# ADC.net
KiCad netlist of a schematic drawn in Altium Designer
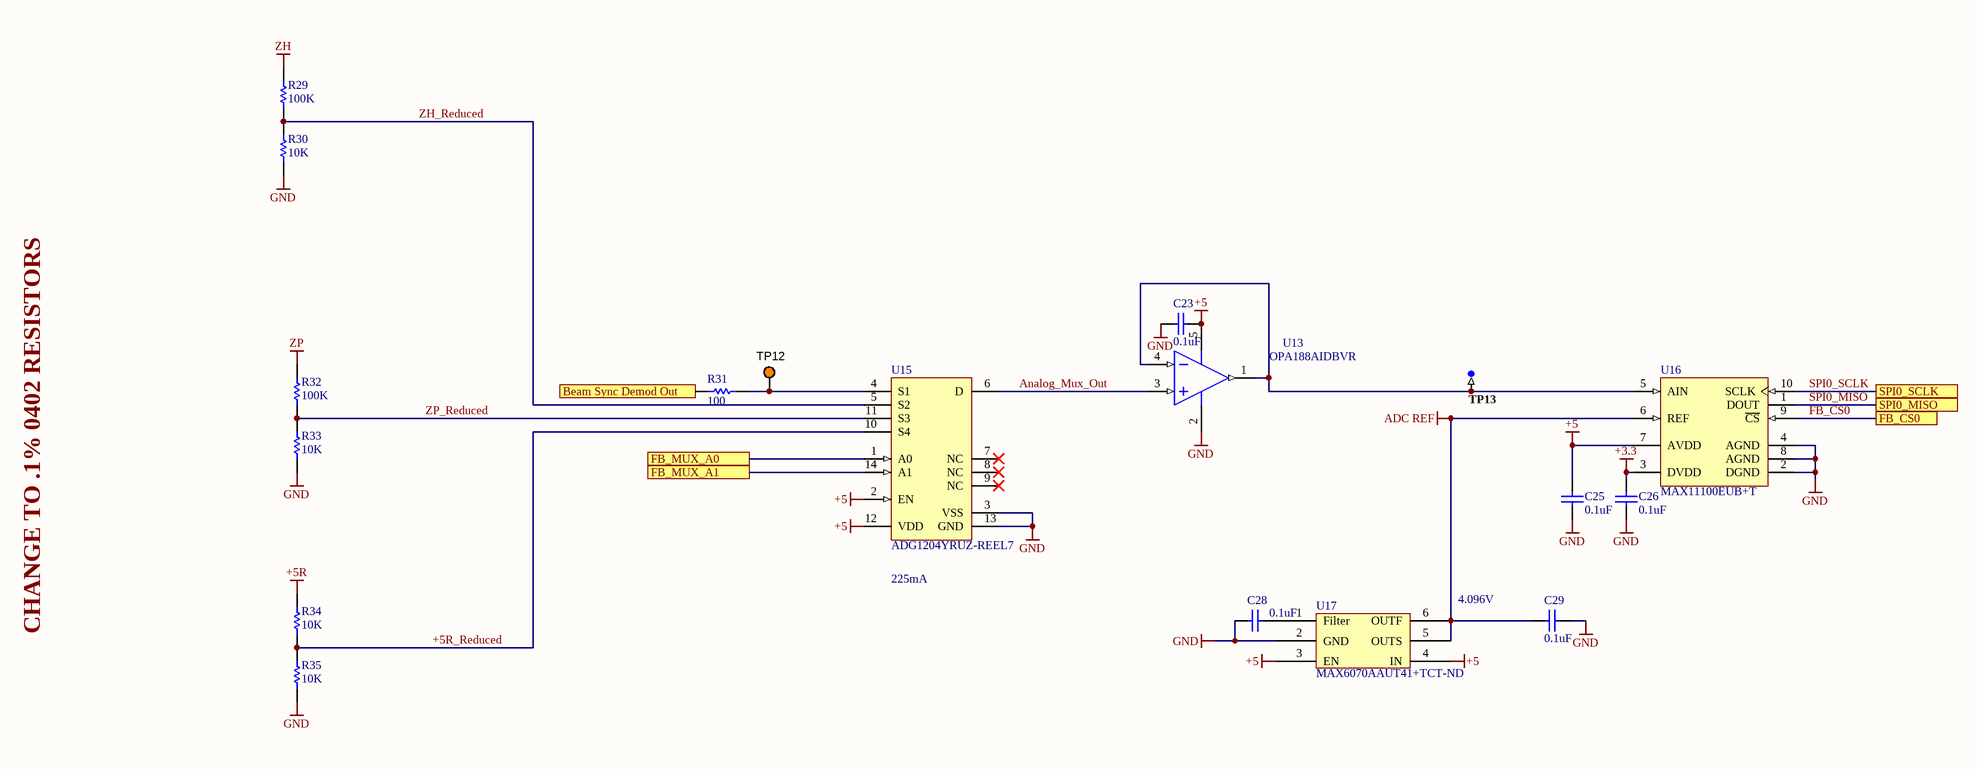
[diagram p0: ADC.SchDoc]

(export (version "E")
  (design (tool "Eeschema 10.0.6"))
  (components
    (comp (ref "C23")
      (value "0.1uF")
      (footprint "CAPC0402(1005)60_L")
      (description "CAP CER 0.1UF 10V X7R 0402")
      (fields
        (field (name "MANUFACTURER") "Murata Electronics North America")
        (field (name "MANUFACTURER PART NUMBER") "GRM155R71A104KA01D")
      )
      (libsource (lib "Altium Content Vault") (part "CMP-1034-00252-1"))
    )
    (comp (ref "C25")
      (value "0.1uF")
      (footprint "CAPC0402(1005)60_L")
      (description "CAP CER 0.1UF 10V X7R 0402")
      (fields
        (field (name "MANUFACTURER") "Murata Electronics North America")
        (field (name "MANUFACTURER PART NUMBER") "GRM155R71A104KA01D")
      )
      (libsource (lib "Altium Content Vault") (part "CMP-1034-00252-1"))
    )
    (comp (ref "C26")
      (value "0.1uF")
      (footprint "CAPC0402(1005)60_L")
      (description "CAP CER 0.1UF 10V X7R 0402")
      (fields
        (field (name "MANUFACTURER") "Murata Electronics North America")
        (field (name "MANUFACTURER PART NUMBER") "GRM155R71A104KA01D")
      )
      (libsource (lib "Altium Content Vault") (part "CMP-1034-00252-1"))
    )
    (comp (ref "C28")
      (value "0.1uF")
      (footprint "CAPC0402(1005)60_L")
      (description "CAP CER 0.1UF 10V X7R 0402")
      (fields
        (field (name "MANUFACTURER") "Murata Electronics North America")
        (field (name "MANUFACTURER PART NUMBER") "GRM155R71A104KA01D")
      )
      (libsource (lib "Altium Content Vault") (part "CMP-1034-00252-1"))
    )
    (comp (ref "C29")
      (value "0.1uF")
      (footprint "CAPC0402(1005)60_L")
      (description "CAP CER 0.1UF 10V X7R 0402")
      (fields
        (field (name "MANUFACTURER") "Murata Electronics North America")
        (field (name "MANUFACTURER PART NUMBER") "GRM155R71A104KA01D")
      )
      (libsource (lib "Altium Content Vault") (part "CMP-1034-00252-1"))
    )
    (comp (ref "R29")
      (value "100K")
      (footprint "RESC0805(2012)_L")
      (description "RES SMD 100K OHM 1% 1/8W 0805")
      (fields
        (field (name "MANUFACTURER") "Vishay Dale")
        (field (name "MANUFACTURER PART NUMBER") "RCA0805100KFKEA")
      )
      (libsource (lib "Altium Content Vault") (part "CMP-1013-00215-1"))
    )
    (comp (ref "R30")
      (value "10K")
      (footprint "RESC0805(2012)_L")
      (description "RES SMD 10K OHM 1% 1/8W 0805")
      (fields
        (field (name "MANUFACTURER") "Vishay Dale")
        (field (name "MANUFACTURER PART NUMBER") "CRCW080510K0FKEA")
      )
      (libsource (lib "Altium Content Vault") (part "CMP-1013-00215-1"))
    )
    (comp (ref "R31")
      (value "100")
      (footprint "RESC0805(2012)_L")
      (description "RES SMD 100 OHM 1% 1/8W 0805")
      (libsource (lib "Altium Content Vault") (part "CMP-1013-00215-1"))
    )
    (comp (ref "R32")
      (value "100K")
      (footprint "RESC0805(2012)_L")
      (description "RES SMD 100K OHM 1% 1/8W 0805")
      (fields
        (field (name "MANUFACTURER") "Vishay Dale")
        (field (name "MANUFACTURER PART NUMBER") "RCA0805100KFKEA")
      )
      (libsource (lib "Altium Content Vault") (part "CMP-1013-00215-1"))
    )
    (comp (ref "R33")
      (value "10K")
      (footprint "RESC0805(2012)_L")
      (description "RES SMD 10K OHM 1% 1/8W 0805")
      (fields
        (field (name "MANUFACTURER") "Vishay Dale")
        (field (name "MANUFACTURER PART NUMBER") "CRCW080510K0FKEA")
      )
      (libsource (lib "Altium Content Vault") (part "CMP-1013-00215-1"))
    )
    (comp (ref "R34")
      (value "10K")
      (footprint "RESC0805(2012)_L")
      (description "RES SMD 10K OHM 1% 1/8W 0805")
      (fields
        (field (name "MANUFACTURER") "Vishay Dale")
        (field (name "MANUFACTURER PART NUMBER") "CRCW080510K0FKEA")
      )
      (libsource (lib "Altium Content Vault") (part "CMP-1013-00215-1"))
    )
    (comp (ref "R35")
      (value "10K")
      (footprint "RESC0805(2012)_L")
      (description "RES SMD 10K OHM 1% 1/8W 0805")
      (fields
        (field (name "MANUFACTURER") "Vishay Dale")
        (field (name "MANUFACTURER PART NUMBER") "CRCW080510K0FKEA")
      )
      (libsource (lib "Altium Content Vault") (part "CMP-1013-00215-1"))
    )
    (comp (ref "TP12")
      (value "5003")
      (footprint "KSTN-5003")
      (description "Test Point, Orange, 1-Pin THD, RoHS")
      (libsource (lib "Altium Content Vault") (part "CMP-1672-00009-1"))
    )
    (comp (ref "TP13")
      (value "TP-SM-C-100")
      (footprint "TP-SM-C-100")
      (description "Test Point, Surface Mount, Circular, Pad Diameter 1 mm")
      (fields (field (name "MANUFACTURER") "No Vendor"))
      (libsource (lib "Altium Content Vault") (part "CMP-0484-00002-2"))
    )
    (comp (ref "U13")
      (value "OPA188AIDBVR")
      (footprint "DBV0005A_M")
      (fields (field (name "MANUFACTURER") "Texas Instruments"))
      (libsource (lib "Altium Content Vault") (part "CMP-0809-00005-2"))
    )
    (comp (ref "U15")
      (value "ADG1204YRUZ-REEL7")
      (footprint "ADI-RU-14_L")
      (fields
        (field (name "MANUFACTURER") "Maxim Integrated")
        (field (name "MANUFACTURER PART NUMBER") "MAX11100EUB+")
        (field (name "BASE PART NUMBER") "MAX11100")
      )
      (libsource (lib "Altium Content Vault") (part "CMP-0793-00109-1"))
    )
    (comp (ref "U16")
      (value "MAX11100EUB+T")
      (footprint "U10+2_L")
      (description "16-Bit, +5V, 200ksps ADC with 10uA Shutdown, 10-Pin uMAX, -40°C to +85°C, Pb-Free, Tape and Reel")
      (fields
        (field (name "MANUFACTURER") "Maxim Integrated")
        (field (name "MANUFACTURER PART NUMBER") "MAX11100EUB+")
      )
      (libsource (lib "Altium Content Vault") (part "CMP-0249-00017-1"))
    )
    (comp (ref "U17")
      (value "MAX6070AAUT41+T")
      (footprint "SOT95P280X445-6N")
      (description "IC VREF SERIES 4.096V SOT23")
      (fields
        (field (name "SUPPLIER PART NUMBER 1") "MAX6070AAUT41+TCT-ND")
        (field (name "MANUFACTURER") "Maxim Integrated")
        (field (name "TOLERANCE") "±0.04%")
      )
      (libsource (lib "ZLS_Schematic_lib") (part "MAX6070AAUT41+T"))
    )
  )
  (nets
    (net (code "1") (name "+3.3") (class "Default")
      (node (ref "C26") (pin "2") (pinfunction "2_2") (pintype "passive"))
      (node (ref "U16") (pin "3") (pinfunction "DVDD_3") (pintype "power_in"))
    )
    (net (code "2") (name "+5") (class "Default")
      (node (ref "C23") (pin "2") (pinfunction "2_2") (pintype "passive"))
      (node (ref "C25") (pin "2") (pinfunction "2_2") (pintype "passive"))
      (node (ref "U13") (pin "5") (pinfunction "V+_5") (pintype "power_in"))
      (node (ref "U15") (pin "12") (pinfunction "VDD_12") (pintype "power_in"))
      (node (ref "U15") (pin "2") (pinfunction "EN_2") (pintype "input"))
      (node (ref "U16") (pin "7") (pinfunction "AVDD_7") (pintype "power_in"))
      (node (ref "U17") (pin "3") (pinfunction "EN_3") (pintype "passive"))
      (node (ref "U17") (pin "4") (pinfunction "IN_4") (pintype "passive"))
    )
    (net (code "3") (name "+5R") (class "Default")
      (node (ref "R34") (pin "2") (pinfunction "2_2") (pintype "passive"))
    )
    (net (code "4") (name "/+5R_Reduced") (class "Default")
      (node (ref "R34") (pin "1") (pinfunction "1_1") (pintype "passive"))
      (node (ref "R35") (pin "2") (pinfunction "2_2") (pintype "passive"))
      (node (ref "U15") (pin "10") (pinfunction "S4_10") (pintype "passive"))
    )
    (net (code "5") (name "/Analog_Mux_Out") (class "Default")
      (node (ref "U13") (pin "3") (pinfunction "IN+_3") (pintype "input"))
      (node (ref "U15") (pin "6") (pinfunction "D_6") (pintype "passive"))
    )
    (net (code "6") (name "/Beam Sync Demod Out") (class "Default")
      (node (ref "R31") (pin "2") (pinfunction "2_2") (pintype "passive"))
    )
    (net (code "7") (name "/FB_CS0") (class "Default")
      (node (ref "U16") (pin "9") (pinfunction "~{CS}_9") (pintype "input"))
    )
    (net (code "8") (name "/FB_MUX_A0") (class "Default")
      (node (ref "U15") (pin "1") (pinfunction "A0_1") (pintype "input"))
    )
    (net (code "9") (name "/FB_MUX_A1") (class "Default")
      (node (ref "U15") (pin "14") (pinfunction "A1_14") (pintype "input"))
    )
    (net (code "10") (name "/SPI0_MISO") (class "Default")
      (node (ref "U16") (pin "1") (pinfunction "DOUT_1") (pintype "tri_state"))
    )
    (net (code "11") (name "/SPI0_SCLK") (class "Default")
      (node (ref "U16") (pin "10") (pinfunction "SCLK_10") (pintype "input"))
    )
    (net (code "12") (name "/ZH_Reduced") (class "Default")
      (node (ref "R29") (pin "1") (pinfunction "1_1") (pintype "passive"))
      (node (ref "R30") (pin "2") (pinfunction "2_2") (pintype "passive"))
      (node (ref "U15") (pin "5") (pinfunction "S2_5") (pintype "passive"))
    )
    (net (code "13") (name "/ZP_Reduced") (class "Default")
      (node (ref "R32") (pin "1") (pinfunction "1_1") (pintype "passive"))
      (node (ref "R33") (pin "2") (pinfunction "2_2") (pintype "passive"))
      (node (ref "U15") (pin "11") (pinfunction "S3_11") (pintype "passive"))
    )
    (net (code "14") (name "ADC REF") (class "Default")
      (node (ref "C29") (pin "1") (pinfunction "1_1") (pintype "passive"))
      (node (ref "U16") (pin "6") (pinfunction "REF_6") (pintype "input"))
      (node (ref "U17") (pin "5") (pinfunction "OUTS_5") (pintype "passive"))
      (node (ref "U17") (pin "6") (pinfunction "OUTF_6") (pintype "passive"))
    )
    (net (code "15") (name "GND") (class "Default")
      (node (ref "C23") (pin "1") (pinfunction "1_1") (pintype "passive"))
      (node (ref "C25") (pin "1") (pinfunction "1_1") (pintype "passive"))
      (node (ref "C26") (pin "1") (pinfunction "1_1") (pintype "passive"))
      (node (ref "C28") (pin "1") (pinfunction "1_1") (pintype "passive"))
      (node (ref "C29") (pin "2") (pinfunction "2_2") (pintype "passive"))
      (node (ref "R30") (pin "1") (pinfunction "1_1") (pintype "passive"))
      (node (ref "R33") (pin "1") (pinfunction "1_1") (pintype "passive"))
      (node (ref "R35") (pin "1") (pinfunction "1_1") (pintype "passive"))
      (node (ref "U13") (pin "2") (pinfunction "V-_2") (pintype "power_in"))
      (node (ref "U15") (pin "13") (pinfunction "GND_13") (pintype "power_in"))
      (node (ref "U15") (pin "3") (pinfunction "VSS_3") (pintype "power_in"))
      (node (ref "U16") (pin "2") (pinfunction "DGND_2") (pintype "power_in"))
      (node (ref "U16") (pin "4") (pinfunction "AGND_4") (pintype "power_in"))
      (node (ref "U16") (pin "8") (pinfunction "AGND_8") (pintype "power_in"))
      (node (ref "U17") (pin "2") (pinfunction "GND_2") (pintype "passive"))
    )
    (net (code "16") (name "Net-(U13-IN-)") (class "Default")
      (node (ref "TP13") (pin "1") (pinfunction "1_1") (pintype "input"))
      (node (ref "U13") (pin "1") (pinfunction "OUT_1") (pintype "output"))
      (node (ref "U13") (pin "4") (pinfunction "IN-_4") (pintype "input"))
      (node (ref "U16") (pin "5") (pinfunction "AIN_5") (pintype "input"))
    )
    (net (code "17") (name "Net-(U15-S1)") (class "Default")
      (node (ref "R31") (pin "1") (pinfunction "1_1") (pintype "passive"))
      (node (ref "TP12") (pin "1") (pinfunction "1_1") (pintype "passive"))
      (node (ref "U15") (pin "4") (pinfunction "S1_4") (pintype "passive"))
    )
    (net (code "18") (name "Net-(U17-Filter)") (class "Default")
      (node (ref "C28") (pin "2") (pinfunction "2_2") (pintype "passive"))
      (node (ref "U17") (pin "1") (pinfunction "Filter_1") (pintype "passive"))
    )
    (net (code "19") (name "ZH") (class "Default")
      (node (ref "R29") (pin "2") (pinfunction "2_2") (pintype "passive"))
    )
    (net (code "20") (name "ZP") (class "Default")
      (node (ref "R32") (pin "2") (pinfunction "2_2") (pintype "passive"))
    )
    (net (code "21") (name "unconnected-(U15-NC-Pad7)") (class "Default")
      (node (ref "U15") (pin "7") (pinfunction "NC_7") (pintype "passive+no_connect"))
    )
    (net (code "22") (name "unconnected-(U15-NC-Pad8)") (class "Default")
      (node (ref "U15") (pin "8") (pinfunction "NC_8") (pintype "passive+no_connect"))
    )
    (net (code "23") (name "unconnected-(U15-NC-Pad9)") (class "Default")
      (node (ref "U15") (pin "9") (pinfunction "NC_9") (pintype "passive+no_connect"))
    )
  )
)
